# Dual_P_Variable_Power_Supply.net
KiCad netlist of a schematic drawn in Altium Designer
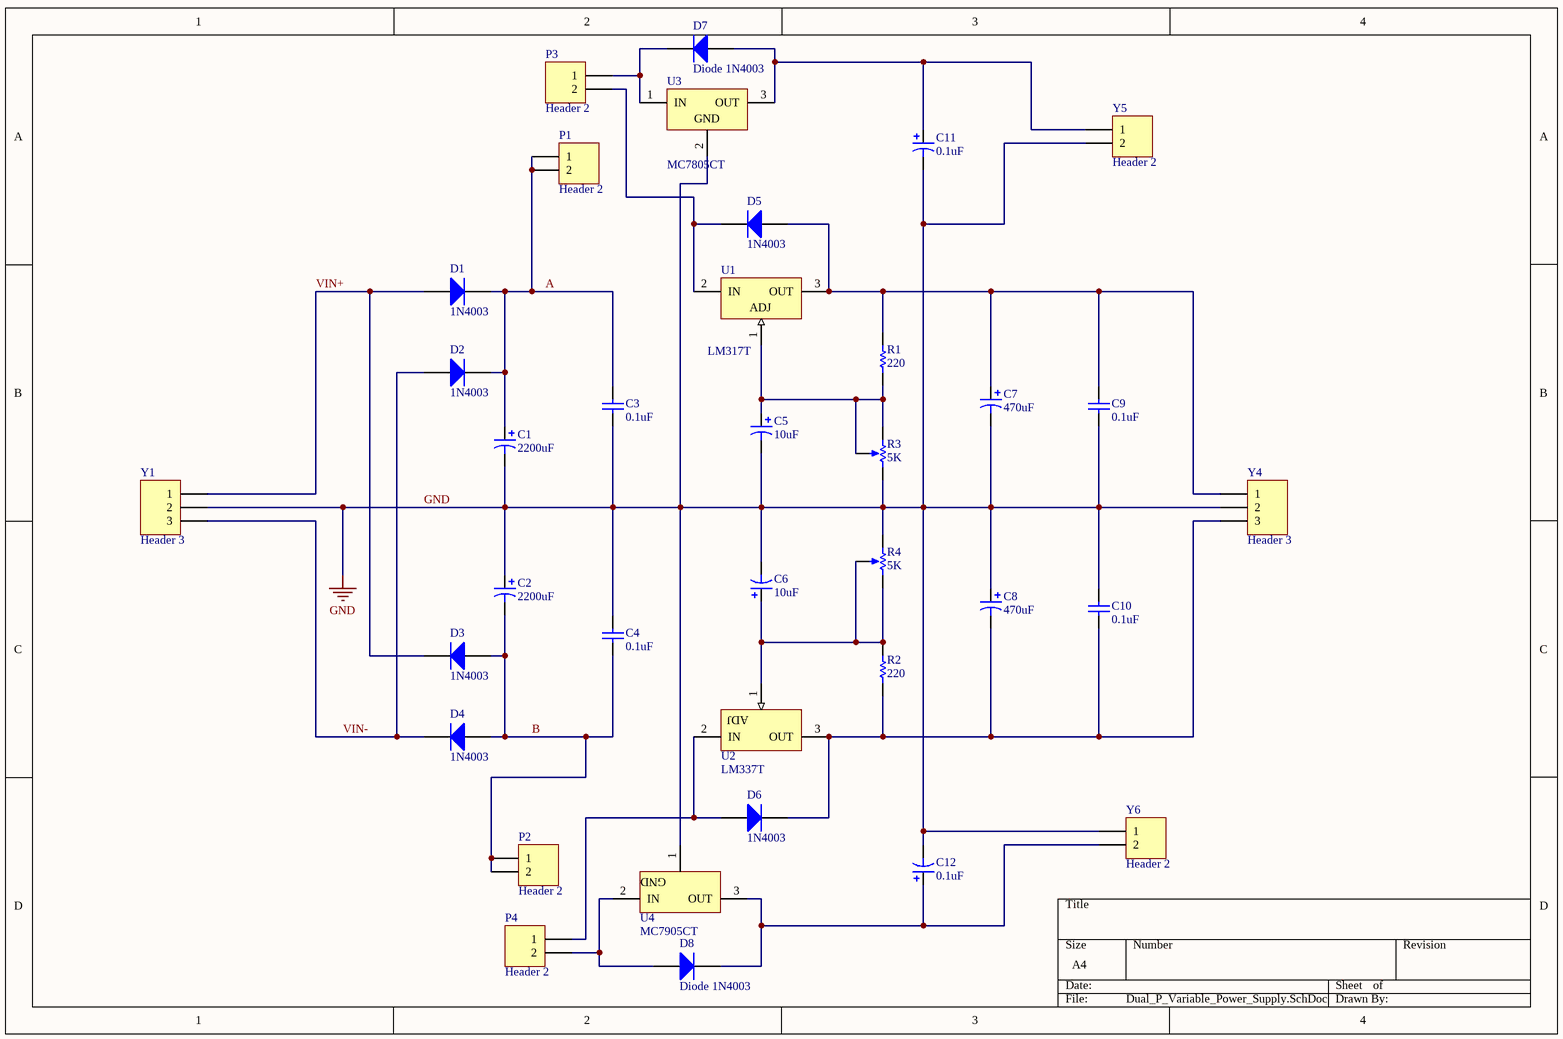
[diagram p0: Dual_P_Variable_Power_Supply.SchDoc]

(export (version "E")
  (design (tool "Eeschema 10.0.6"))
  (components
    (comp (ref "C1")
      (value "2200uF")
      (footprint "RB7.6-15")
      (description "Polarized Capacitor (Radial)")
      (fields (field (name "VOLTAGE") "35V") (field (name "PUBLISHER") "Altium Limited"))
      (libsource (lib "Miscellaneous Devices") (part "Cap Pol1"))
    )
    (comp (ref "C2")
      (value "2200uF")
      (footprint "RB7.6-15")
      (description "Polarized Capacitor (Radial)")
      (fields (field (name "VOLTAGE") "35V") (field (name "PUBLISHER") "Altium Limited"))
      (libsource (lib "Miscellaneous Devices") (part "Cap Pol1"))
    )
    (comp (ref "C3")
      (value "0.1uF")
      (footprint "RAD-0.3")
      (description "Capacitor")
      (fields (field (name "VOLTAGE") "50V") (field (name "PUBLISHER") "Altium Limited"))
      (libsource (lib "Miscellaneous Devices") (part "Cap"))
    )
    (comp (ref "C4")
      (value "0.1uF")
      (footprint "RAD-0.3")
      (description "Capacitor")
      (fields (field (name "VOLTAGE") "50V") (field (name "PUBLISHER") "Altium Limited"))
      (libsource (lib "Miscellaneous Devices") (part "Cap"))
    )
    (comp (ref "C5")
      (value "10uF")
      (footprint "RB7.6-15")
      (description "Polarized Capacitor (Radial)")
      (fields (field (name "VOLTAGE") "35V") (field (name "PUBLISHER") "Altium Limited"))
      (libsource (lib "Miscellaneous Devices") (part "Cap Pol1"))
    )
    (comp (ref "C6")
      (value "10uF")
      (footprint "RB7.6-15")
      (description "Polarized Capacitor (Radial)")
      (fields (field (name "VOLTAGE") "35V") (field (name "PUBLISHER") "Altium Limited"))
      (libsource (lib "Miscellaneous Devices") (part "Cap Pol1"))
    )
    (comp (ref "C7")
      (value "470uF")
      (footprint "RB7.6-15")
      (description "Polarized Capacitor (Radial)")
      (fields (field (name "VOLTAGE") "35V") (field (name "PUBLISHER") "Altium Limited"))
      (libsource (lib "Miscellaneous Devices") (part "Cap Pol1"))
    )
    (comp (ref "C8")
      (value "470uF")
      (footprint "RB7.6-15")
      (description "Polarized Capacitor (Radial)")
      (fields (field (name "VOLTAGE") "35V") (field (name "PUBLISHER") "Altium Limited"))
      (libsource (lib "Miscellaneous Devices") (part "Cap Pol1"))
    )
    (comp (ref "C9")
      (value "0.1uF")
      (footprint "RAD-0.3")
      (description "Capacitor")
      (fields (field (name "VOLTAGE") "50V") (field (name "PUBLISHER") "Altium Limited"))
      (libsource (lib "Miscellaneous Devices") (part "Cap"))
    )
    (comp (ref "C10")
      (value "0.1uF")
      (footprint "RAD-0.3")
      (description "Capacitor")
      (fields (field (name "VOLTAGE") "50V") (field (name "PUBLISHER") "Altium Limited"))
      (libsource (lib "Miscellaneous Devices") (part "Cap"))
    )
    (comp (ref "C11")
      (value "0.1uF")
      (footprint "RB7.6-15")
      (description "Polarized Capacitor (Radial)")
      (fields (field (name "PUBLISHER") "Altium Limited"))
      (libsource (lib "") (part "Cap Pol1_1"))
    )
    (comp (ref "C12")
      (value "0.1uF")
      (footprint "RB7.6-15")
      (description "Polarized Capacitor (Radial)")
      (fields (field (name "PUBLISHER") "Altium Limited"))
      (libsource (lib "Miscellaneous Devices") (part "Cap Pol1"))
    )
    (comp (ref "D1")
      (value "1N4003")
      (footprint "DO-41")
      (description "1 Amp General Purpose Rectifier")
      (fields (field (name "PUBLISHER") "Altium Limited"))
      (libsource (lib "Miscellaneous Devices") (part "Diode 1N4003"))
    )
    (comp (ref "D2")
      (value "1N4003")
      (footprint "DO-41")
      (description "1 Amp General Purpose Rectifier")
      (fields (field (name "PUBLISHER") "Altium Limited"))
      (libsource (lib "Miscellaneous Devices") (part "Diode 1N4003"))
    )
    (comp (ref "D3")
      (value "1N4003")
      (footprint "DO-41")
      (description "1 Amp General Purpose Rectifier")
      (fields (field (name "PUBLISHER") "Altium Limited"))
      (libsource (lib "Miscellaneous Devices") (part "Diode 1N4003"))
    )
    (comp (ref "D4")
      (value "1N4003")
      (footprint "DO-41")
      (description "1 Amp General Purpose Rectifier")
      (fields (field (name "PUBLISHER") "Altium Limited"))
      (libsource (lib "Miscellaneous Devices") (part "Diode 1N4003"))
    )
    (comp (ref "D5")
      (value "1N4003")
      (footprint "DO-41")
      (description "1 Amp General Purpose Rectifier")
      (fields (field (name "PUBLISHER") "Altium Limited"))
      (libsource (lib "Miscellaneous Devices") (part "Diode 1N4003"))
    )
    (comp (ref "D6")
      (value "1N4003")
      (footprint "DO-41")
      (description "1 Amp General Purpose Rectifier")
      (fields (field (name "PUBLISHER") "Altium Limited"))
      (libsource (lib "Miscellaneous Devices") (part "Diode 1N4003"))
    )
    (comp (ref "D7")
      (value "Diode 1N4003")
      (footprint "DO-41")
      (description "1 Amp General Purpose Rectifier")
      (fields (field (name "PUBLISHER") "Altium Limited"))
      (libsource (lib "Miscellaneous Devices") (part "Diode 1N4003"))
    )
    (comp (ref "D8")
      (value "Diode 1N4003")
      (footprint "DO-41")
      (description "1 Amp General Purpose Rectifier")
      (fields (field (name "PUBLISHER") "Altium Limited"))
      (libsource (lib "Miscellaneous Devices") (part "Diode 1N4003"))
    )
    (comp (ref "P1")
      (value "Header 2")
      (footprint "HDR1X2")
      (description "Header, 2-Pin")
      (fields (field (name "PUBLISHER") "Altium Limited"))
      (libsource (lib "Miscellaneous Connectors") (part "Header 2"))
    )
    (comp (ref "P2")
      (value "Header 2")
      (footprint "HDR1X2")
      (description "Header, 2-Pin")
      (fields (field (name "PUBLISHER") "Altium Limited"))
      (libsource (lib "Miscellaneous Connectors") (part "Header 2"))
    )
    (comp (ref "P3")
      (value "Header 2")
      (footprint "HDR1X2")
      (description "Header, 2-Pin")
      (fields (field (name "PUBLISHER") "Altium Limited"))
      (libsource (lib "") (part "Header 2_1"))
    )
    (comp (ref "P4")
      (value "Header 2")
      (footprint "HDR1X2")
      (description "Header, 2-Pin")
      (fields (field (name "PUBLISHER") "Altium Limited"))
      (libsource (lib "") (part "Header 2_1"))
    )
    (comp (ref "R1")
      (value "220")
      (footprint "AXIAL-0.3")
      (description "Resistor")
      (fields (field (name "PUBLISHER") "Altium Limited"))
      (libsource (lib "Miscellaneous Devices") (part "Res1"))
    )
    (comp (ref "R2")
      (value "220")
      (footprint "AXIAL-0.3")
      (description "Resistor")
      (fields (field (name "PUBLISHER") "Altium Limited"))
      (libsource (lib "Miscellaneous Devices") (part "Res1"))
    )
    (comp (ref "R3")
      (value "5K")
      (footprint "VR5")
      (description "Potentiometer")
      (fields (field (name "PUBLISHER") "Altium Limited"))
      (libsource (lib "Miscellaneous Devices") (part "RPot"))
    )
    (comp (ref "R4")
      (value "5K")
      (footprint "VR5")
      (description "Potentiometer")
      (fields (field (name "PUBLISHER") "Altium Limited"))
      (libsource (lib "Miscellaneous Devices") (part "RPot"))
    )
    (comp (ref "U1")
      (value "LM317T")
      (footprint "TO220ABN")
      (description "1.2V to 37V Voltage Regulator")
      (fields (field (name "PUBLISHER") "Altium Limited"))
      (libsource (lib "ST Power Mgt Voltage Regulator") (part "LM317T"))
    )
    (comp (ref "U2")
      (value "LM337T")
      (footprint "221A-04")
      (description "3-Terminal Adjustable Negative Voltage Regulator")
      (fields (field (name "PUBLISHER") "Altium Limited"))
      (libsource (lib "Motorola Power Mgt Voltage Regulator") (part "LM337T"))
    )
    (comp (ref "U3")
      (value "MC7805CT")
      (footprint "221A-04")
      (description "3-Terminal Positive Fixed Voltage Regulator")
      (fields (field (name "PUBLISHER") "Altium Limited"))
      (libsource (lib "Motorola Power Mgt Voltage Regulator") (part "MC7805CT"))
    )
    (comp (ref "U4")
      (value "MC7905CT")
      (footprint "221A-04")
      (description "Three-Terminal Negative Fixed Voltage Regulator")
      (fields (field (name "PUBLISHER") "Altium Limited"))
      (libsource (lib "Motorola Power Mgt Voltage Regulator") (part "MC7905CT"))
    )
    (comp (ref "Y1")
      (value "Header 3")
      (footprint "HDR1X3")
      (description "Header, 3-Pin")
      (fields (field (name "PUBLISHER") "Altium Limited"))
      (libsource (lib "Miscellaneous Connectors") (part "Header 3"))
    )
    (comp (ref "Y4")
      (value "Header 3")
      (footprint "HDR1X3")
      (description "Header, 3-Pin")
      (fields (field (name "PUBLISHER") "Altium Limited"))
      (libsource (lib "") (part "Header 3_1"))
    )
    (comp (ref "Y5")
      (value "Header 2")
      (footprint "HDR1X2")
      (description "Header, 2-Pin")
      (fields (field (name "PUBLISHER") "Altium Limited"))
      (libsource (lib "Miscellaneous Connectors") (part "Header 2"))
    )
    (comp (ref "Y6")
      (value "Header 2")
      (footprint "HDR1X2")
      (description "Header, 2-Pin")
      (fields (field (name "PUBLISHER") "Altium Limited"))
      (libsource (lib "Miscellaneous Connectors") (part "Header 2"))
    )
  )
  (nets
    (net (code "1") (name "/A") (class "Default")
      (node (ref "C1") (pin "1") (pinfunction "1_1") (pintype "passive"))
      (node (ref "C3") (pin "2") (pinfunction "2_2") (pintype "passive"))
      (node (ref "D1") (pin "2") (pinfunction "K_2") (pintype "passive"))
      (node (ref "D2") (pin "2") (pinfunction "K_2") (pintype "passive"))
      (node (ref "P1") (pin "1") (pinfunction "1_1") (pintype "passive"))
      (node (ref "P1") (pin "2") (pinfunction "2_2") (pintype "passive"))
    )
    (net (code "2") (name "/B") (class "Default")
      (node (ref "C2") (pin "2") (pinfunction "2_2") (pintype "passive"))
      (node (ref "C4") (pin "1") (pinfunction "1_1") (pintype "passive"))
      (node (ref "D3") (pin "1") (pinfunction "A_1") (pintype "passive"))
      (node (ref "D4") (pin "1") (pinfunction "A_1") (pintype "passive"))
      (node (ref "P2") (pin "1") (pinfunction "1_1") (pintype "passive"))
      (node (ref "P2") (pin "2") (pinfunction "2_2") (pintype "passive"))
    )
    (net (code "3") (name "/VIN+") (class "Default")
      (node (ref "D1") (pin "1") (pinfunction "A_1") (pintype "passive"))
      (node (ref "D3") (pin "2") (pinfunction "K_2") (pintype "passive"))
      (node (ref "Y1") (pin "1") (pinfunction "1_1") (pintype "passive"))
    )
    (net (code "4") (name "/VIN-") (class "Default")
      (node (ref "D2") (pin "1") (pinfunction "A_1") (pintype "passive"))
      (node (ref "D4") (pin "2") (pinfunction "K_2") (pintype "passive"))
      (node (ref "Y1") (pin "3") (pinfunction "3_3") (pintype "passive"))
    )
    (net (code "5") (name "GND") (class "Default")
      (node (ref "C1") (pin "2") (pinfunction "2_2") (pintype "passive"))
      (node (ref "C10") (pin "2") (pinfunction "2_2") (pintype "passive"))
      (node (ref "C11") (pin "2") (pinfunction "2_2") (pintype "passive"))
      (node (ref "C12") (pin "2") (pinfunction "2_2") (pintype "passive"))
      (node (ref "C2") (pin "1") (pinfunction "1_1") (pintype "passive"))
      (node (ref "C3") (pin "1") (pinfunction "1_1") (pintype "passive"))
      (node (ref "C4") (pin "2") (pinfunction "2_2") (pintype "passive"))
      (node (ref "C5") (pin "2") (pinfunction "2_2") (pintype "passive"))
      (node (ref "C6") (pin "2") (pinfunction "2_2") (pintype "passive"))
      (node (ref "C7") (pin "2") (pinfunction "2_2") (pintype "passive"))
      (node (ref "C8") (pin "1") (pinfunction "1_1") (pintype "passive"))
      (node (ref "C9") (pin "1") (pinfunction "1_1") (pintype "passive"))
      (node (ref "R3") (pin "2") (pinfunction "BOT_2") (pintype "passive"))
      (node (ref "R4") (pin "1") (pinfunction "TOP_1") (pintype "passive"))
      (node (ref "U3") (pin "2") (pinfunction "GND_2") (pintype "power_in"))
      (node (ref "U4") (pin "1") (pinfunction "GND_1") (pintype "power_in"))
      (node (ref "Y1") (pin "2") (pinfunction "2_2") (pintype "passive"))
      (node (ref "Y4") (pin "2") (pinfunction "2_2") (pintype "passive"))
      (node (ref "Y5") (pin "2") (pinfunction "2_2") (pintype "passive"))
      (node (ref "Y6") (pin "1") (pinfunction "1_1") (pintype "passive"))
    )
    (net (code "6") (name "Net-(D5-A)") (class "Default")
      (node (ref "C7") (pin "1") (pinfunction "1_1") (pintype "passive"))
      (node (ref "C9") (pin "2") (pinfunction "2_2") (pintype "passive"))
      (node (ref "D5") (pin "1") (pinfunction "A_1") (pintype "passive"))
      (node (ref "R1") (pin "2") (pinfunction "2_2") (pintype "passive"))
      (node (ref "U1") (pin "3") (pinfunction "OUT_3") (pintype "power_in"))
      (node (ref "Y4") (pin "1") (pinfunction "1_1") (pintype "passive"))
    )
    (net (code "7") (name "Net-(D5-K)") (class "Default")
      (node (ref "D5") (pin "2") (pinfunction "K_2") (pintype "passive"))
      (node (ref "P3") (pin "2") (pinfunction "2_2") (pintype "passive"))
      (node (ref "U1") (pin "2") (pinfunction "IN_2") (pintype "power_in"))
    )
    (net (code "8") (name "Net-(D6-A)") (class "Default")
      (node (ref "D6") (pin "1") (pinfunction "A_1") (pintype "passive"))
      (node (ref "P4") (pin "1") (pinfunction "1_1") (pintype "passive"))
      (node (ref "U2") (pin "2") (pinfunction "IN_2") (pintype "power_in"))
    )
    (net (code "9") (name "Net-(D6-K)") (class "Default")
      (node (ref "C10") (pin "1") (pinfunction "1_1") (pintype "passive"))
      (node (ref "C8") (pin "2") (pinfunction "2_2") (pintype "passive"))
      (node (ref "D6") (pin "2") (pinfunction "K_2") (pintype "passive"))
      (node (ref "R2") (pin "1") (pinfunction "1_1") (pintype "passive"))
      (node (ref "U2") (pin "3") (pinfunction "OUT_3") (pintype "power_in"))
      (node (ref "Y4") (pin "3") (pinfunction "3_3") (pintype "passive"))
    )
    (net (code "10") (name "Net-(D7-A)") (class "Default")
      (node (ref "C11") (pin "1") (pinfunction "1_1") (pintype "passive"))
      (node (ref "D7") (pin "1") (pinfunction "A_1") (pintype "passive"))
      (node (ref "U3") (pin "3") (pinfunction "OUT_3") (pintype "power_in"))
      (node (ref "Y5") (pin "1") (pinfunction "1_1") (pintype "passive"))
    )
    (net (code "11") (name "Net-(D7-K)") (class "Default")
      (node (ref "D7") (pin "2") (pinfunction "K_2") (pintype "passive"))
      (node (ref "P3") (pin "1") (pinfunction "1_1") (pintype "passive"))
      (node (ref "U3") (pin "1") (pinfunction "IN_1") (pintype "power_in"))
    )
    (net (code "12") (name "Net-(D8-A)") (class "Default")
      (node (ref "D8") (pin "1") (pinfunction "A_1") (pintype "passive"))
      (node (ref "P4") (pin "2") (pinfunction "2_2") (pintype "passive"))
      (node (ref "U4") (pin "2") (pinfunction "IN_2") (pintype "power_in"))
    )
    (net (code "13") (name "Net-(D8-K)") (class "Default")
      (node (ref "C12") (pin "1") (pinfunction "1_1") (pintype "passive"))
      (node (ref "D8") (pin "2") (pinfunction "K_2") (pintype "passive"))
      (node (ref "U4") (pin "3") (pinfunction "OUT_3") (pintype "power_in"))
      (node (ref "Y6") (pin "2") (pinfunction "2_2") (pintype "passive"))
    )
    (net (code "14") (name "Net-(R3-TAP)") (class "Default")
      (node (ref "C5") (pin "1") (pinfunction "1_1") (pintype "passive"))
      (node (ref "R1") (pin "1") (pinfunction "1_1") (pintype "passive"))
      (node (ref "R3") (pin "1") (pinfunction "TOP_1") (pintype "passive"))
      (node (ref "R3") (pin "3") (pinfunction "TAP_3") (pintype "passive"))
      (node (ref "U1") (pin "1") (pinfunction "ADJ_1") (pintype "input"))
    )
    (net (code "15") (name "Net-(R4-BOT)") (class "Default")
      (node (ref "C6") (pin "1") (pinfunction "1_1") (pintype "passive"))
      (node (ref "R2") (pin "2") (pinfunction "2_2") (pintype "passive"))
      (node (ref "R4") (pin "2") (pinfunction "BOT_2") (pintype "passive"))
      (node (ref "R4") (pin "3") (pinfunction "TAP_3") (pintype "passive"))
      (node (ref "U2") (pin "1") (pinfunction "ADJ_1") (pintype "input"))
    )
  )
)
